# B_Arduino_MEGA2560_ref.net
KiCad netlist of a schematic drawn in EAGLE
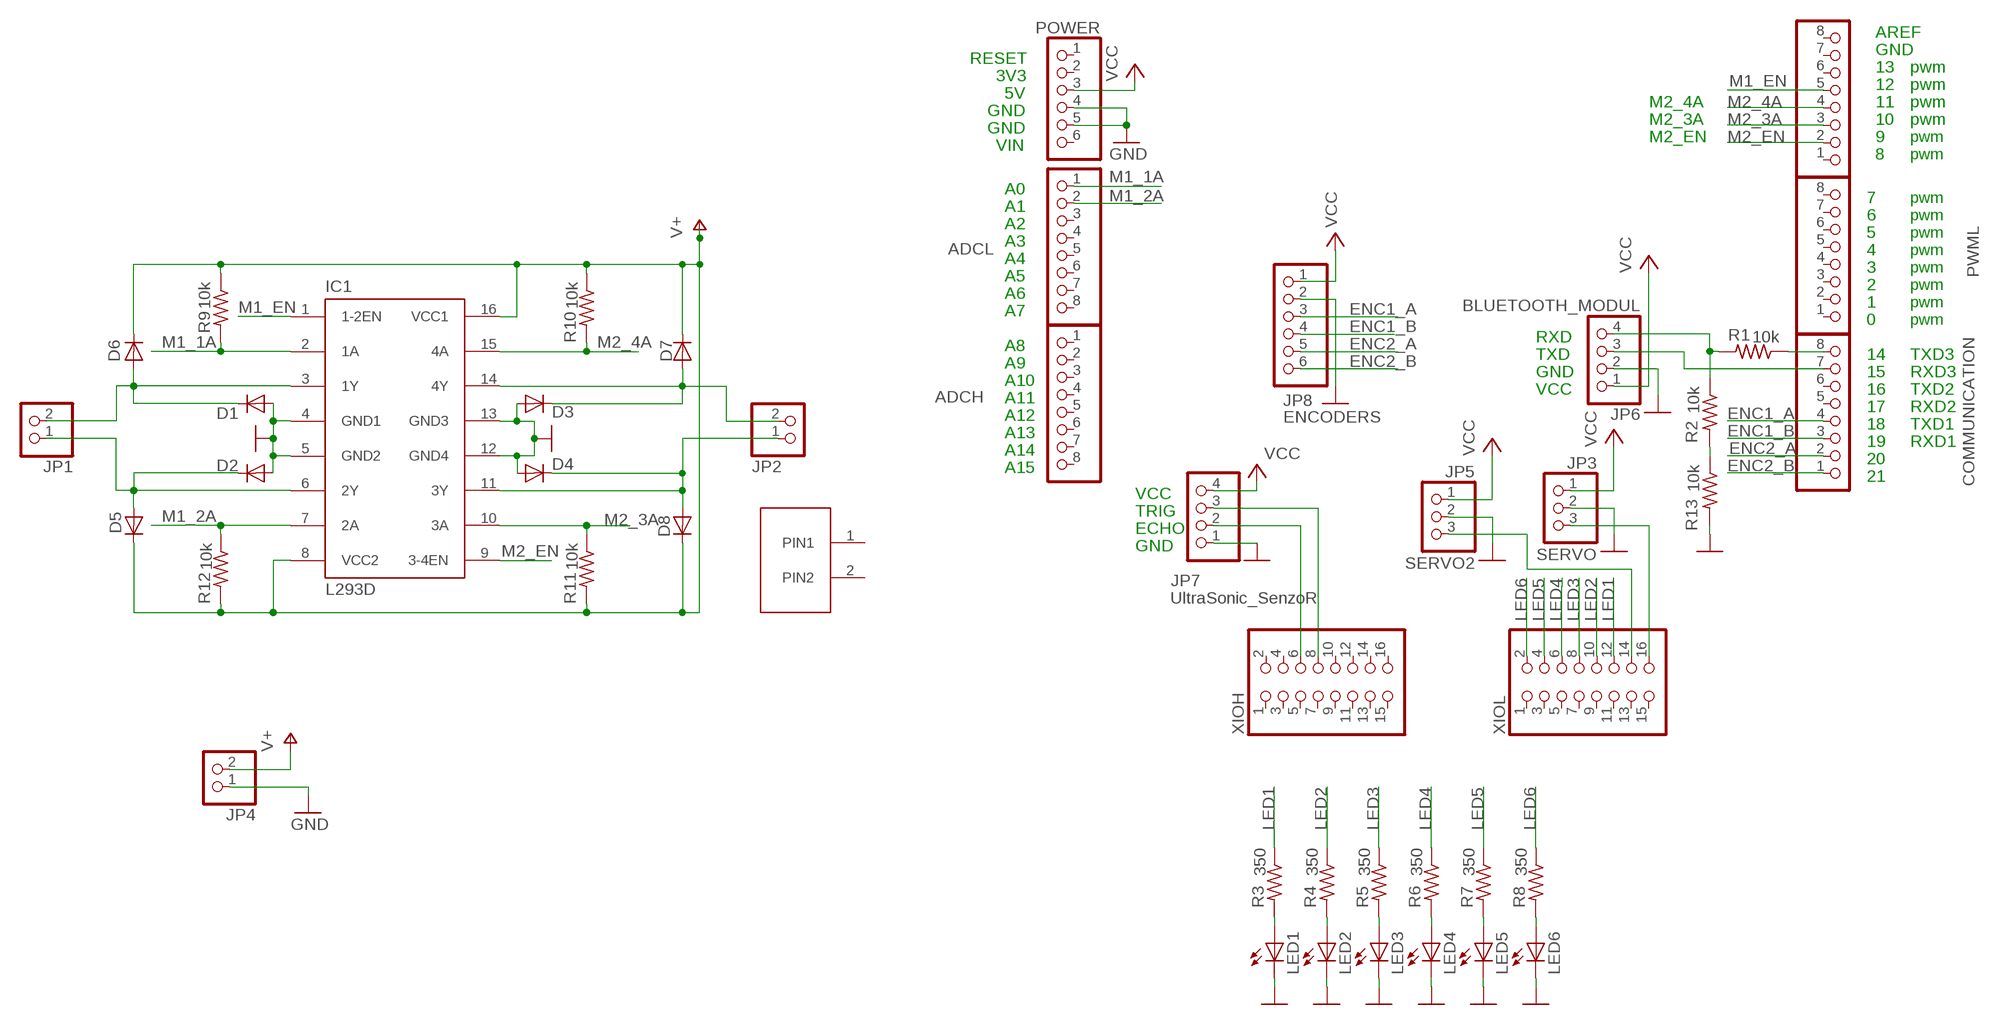
[diagram p0: schematic, sheet 1]

(export (version "E")
  (design (tool "Eeschema 10.0.6"))
  (components
    (comp (ref "ADCH")
      (value "PINHD-1X8")
      (footprint "eagle-import:1X08")
      (libsource (lib "eagle-import") (part "PINHD-1X8"))
    )
    (comp (ref "ADCL")
      (value "PINHD-1X8")
      (footprint "eagle-import:1X08")
      (libsource (lib "eagle-import") (part "PINHD-1X8"))
    )
    (comp (ref "COMMUNICATION")
      (value "PINHD-1X8")
      (footprint "eagle-import:1X08")
      (libsource (lib "eagle-import") (part "PINHD-1X8"))
    )
    (comp (ref "D1")
      (value "PMLL4150")
      (footprint "eagle-import:SOD80C")
      (libsource (lib "eagle-import") (part "PMLL4150"))
    )
    (comp (ref "D2")
      (value "PMLL4150")
      (footprint "eagle-import:SOD80C")
      (libsource (lib "eagle-import") (part "PMLL4150"))
    )
    (comp (ref "D3")
      (value "PMLL4150")
      (footprint "eagle-import:SOD80C")
      (libsource (lib "eagle-import") (part "PMLL4150"))
    )
    (comp (ref "D4")
      (value "PMLL4150")
      (footprint "eagle-import:SOD80C")
      (libsource (lib "eagle-import") (part "PMLL4150"))
    )
    (comp (ref "D5")
      (value "PMLL4150")
      (footprint "eagle-import:SOD80C")
      (libsource (lib "eagle-import") (part "PMLL4150"))
    )
    (comp (ref "D6")
      (value "PMLL4150")
      (footprint "eagle-import:SOD80C")
      (libsource (lib "eagle-import") (part "PMLL4150"))
    )
    (comp (ref "D7")
      (value "PMLL4150")
      (footprint "eagle-import:SOD80C")
      (libsource (lib "eagle-import") (part "PMLL4150"))
    )
    (comp (ref "D8")
      (value "PMLL4150")
      (footprint "eagle-import:SOD80C")
      (libsource (lib "eagle-import") (part "PMLL4150"))
    )
    (comp (ref "IC1")
      (value "L293D")
      (footprint "eagle-import:DIL16")
      (libsource (lib "eagle-import") (part "L293D"))
    )
    (comp (ref "JP1")
      (value "PINHD-1X2")
      (footprint "eagle-import:1X02")
      (libsource (lib "eagle-import") (part "PINHD-1X2"))
    )
    (comp (ref "JP2")
      (value "PINHD-1X2")
      (footprint "eagle-import:1X02")
      (libsource (lib "eagle-import") (part "PINHD-1X2"))
    )
    (comp (ref "JP3")
      (value "SERVO")
      (footprint "eagle-import:1X03")
      (libsource (lib "eagle-import") (part "PINHD-1X3"))
    )
    (comp (ref "JP4")
      (value "PINHD-1X2")
      (footprint "eagle-import:1X02")
      (libsource (lib "eagle-import") (part "PINHD-1X2"))
    )
    (comp (ref "JP5")
      (value "SERVO2")
      (footprint "eagle-import:1X03")
      (libsource (lib "eagle-import") (part "PINHD-1X3"))
    )
    (comp (ref "JP6")
      (value "BLUETOOTH_MODUL")
      (footprint "eagle-import:1X04")
      (libsource (lib "eagle-import") (part "PINHD-1X4"))
    )
    (comp (ref "JP7")
      (value "UltraSonic_SenzoR")
      (footprint "eagle-import:1X04")
      (libsource (lib "eagle-import") (part "PINHD-1X4"))
    )
    (comp (ref "JP8")
      (value "ENCODERS")
      (footprint "eagle-import:1X06")
      (libsource (lib "eagle-import") (part "PINHD-1X6"))
    )
    (comp (ref "LED1")
      (value "LED")
      (footprint "eagle-import:SMARTLED-TTW")
      (libsource (lib "eagle-import") (part "LED"))
    )
    (comp (ref "LED2")
      (value "LED")
      (footprint "eagle-import:SMARTLED-TTW")
      (libsource (lib "eagle-import") (part "LED"))
    )
    (comp (ref "LED3")
      (value "LED")
      (footprint "eagle-import:SMARTLED-TTW")
      (libsource (lib "eagle-import") (part "LED"))
    )
    (comp (ref "LED4")
      (value "LED")
      (footprint "eagle-import:SMARTLED-TTW")
      (libsource (lib "eagle-import") (part "LED"))
    )
    (comp (ref "LED5")
      (value "LED")
      (footprint "eagle-import:SMARTLED-TTW")
      (libsource (lib "eagle-import") (part "LED"))
    )
    (comp (ref "LED6")
      (value "LED")
      (footprint "eagle-import:SMARTLED-TTW")
      (libsource (lib "eagle-import") (part "LED"))
    )
    (comp (ref "POWER")
      (value "PINHD-1X6")
      (footprint "eagle-import:1X06")
      (libsource (lib "eagle-import") (part "PINHD-1X6"))
    )
    (comp (ref "PWMH")
      (value "PINHD-1X8")
      (footprint "eagle-import:1X08")
      (libsource (lib "eagle-import") (part "PINHD-1X8"))
    )
    (comp (ref "PWML")
      (value "PINHD-1X8")
      (footprint "eagle-import:1X08")
      (libsource (lib "eagle-import") (part "PINHD-1X8"))
    )
    (comp (ref "R1")
      (value "10k")
      (footprint "eagle-import:R0805")
      (libsource (lib "eagle-import") (part "R-US_R0805"))
    )
    (comp (ref "R2")
      (value "10k")
      (footprint "eagle-import:R0805")
      (libsource (lib "eagle-import") (part "R-US_R0805"))
    )
    (comp (ref "R3")
      (value "350")
      (footprint "eagle-import:R0805")
      (libsource (lib "eagle-import") (part "R-US_R0805"))
    )
    (comp (ref "R4")
      (value "350")
      (footprint "eagle-import:R0805")
      (libsource (lib "eagle-import") (part "R-US_R0805"))
    )
    (comp (ref "R5")
      (value "350")
      (footprint "eagle-import:R0805")
      (libsource (lib "eagle-import") (part "R-US_R0805"))
    )
    (comp (ref "R6")
      (value "350")
      (footprint "eagle-import:R0805")
      (libsource (lib "eagle-import") (part "R-US_R0805"))
    )
    (comp (ref "R7")
      (value "350")
      (footprint "eagle-import:R0805")
      (libsource (lib "eagle-import") (part "R-US_R0805"))
    )
    (comp (ref "R8")
      (value "350")
      (footprint "eagle-import:R0805")
      (libsource (lib "eagle-import") (part "R-US_R0805"))
    )
    (comp (ref "R9")
      (value "10k")
      (footprint "eagle-import:R0805")
      (libsource (lib "eagle-import") (part "R-US_R0805"))
    )
    (comp (ref "R10")
      (value "10k")
      (footprint "eagle-import:R0805")
      (libsource (lib "eagle-import") (part "R-US_R0805"))
    )
    (comp (ref "R11")
      (value "10k")
      (footprint "eagle-import:R0805")
      (libsource (lib "eagle-import") (part "R-US_R0805"))
    )
    (comp (ref "R12")
      (value "10k")
      (footprint "eagle-import:R0805")
      (libsource (lib "eagle-import") (part "R-US_R0805"))
    )
    (comp (ref "R13")
      (value "10k")
      (footprint "eagle-import:R0805")
      (libsource (lib "eagle-import") (part "R-US_R0805"))
    )
    (comp (ref "U$1")
      (value "FR_L_PNHD_2")
      (footprint "eagle-import:FR_L_PN_HD-2")
      (libsource (lib "eagle-import") (part "FR_L_PNHD_2"))
    )
    (comp (ref "XIOH")
      (value "PINHD-2X8")
      (footprint "eagle-import:2X08")
      (libsource (lib "eagle-import") (part "PINHD-2X8"))
    )
    (comp (ref "XIOL")
      (value "PINHD-2X8")
      (footprint "eagle-import:2X08")
      (libsource (lib "eagle-import") (part "PINHD-2X8"))
    )
  )
  (nets
    (net (code "1") (name "/ENC1_A") (class "Default")
      (node (ref "COMMUNICATION") (pin "4") (pinfunction "4_4") (pintype "passive"))
      (node (ref "JP8") (pin "3") (pinfunction "3_3") (pintype "passive"))
    )
    (net (code "2") (name "/ENC1_B") (class "Default")
      (node (ref "COMMUNICATION") (pin "3") (pinfunction "3_3") (pintype "passive"))
      (node (ref "JP8") (pin "4") (pinfunction "4_4") (pintype "passive"))
    )
    (net (code "3") (name "/ENC2_A") (class "Default")
      (node (ref "COMMUNICATION") (pin "2") (pinfunction "2_2") (pintype "passive"))
      (node (ref "JP8") (pin "5") (pinfunction "5_5") (pintype "passive"))
    )
    (net (code "4") (name "/ENC2_B") (class "Default")
      (node (ref "COMMUNICATION") (pin "1") (pinfunction "1_1") (pintype "passive"))
      (node (ref "JP8") (pin "6") (pinfunction "6_6") (pintype "passive"))
    )
    (net (code "5") (name "/LED1") (class "Default")
      (node (ref "R3") (pin "1") (pinfunction "1_1") (pintype "passive"))
      (node (ref "XIOL") (pin "12") (pinfunction "12_12") (pintype "passive"))
    )
    (net (code "6") (name "/LED2") (class "Default")
      (node (ref "R4") (pin "1") (pinfunction "1_1") (pintype "passive"))
      (node (ref "XIOL") (pin "10") (pinfunction "10_10") (pintype "passive"))
    )
    (net (code "7") (name "/LED3") (class "Default")
      (node (ref "R5") (pin "1") (pinfunction "1_1") (pintype "passive"))
      (node (ref "XIOL") (pin "8") (pinfunction "8_8") (pintype "passive"))
    )
    (net (code "8") (name "/LED4") (class "Default")
      (node (ref "R6") (pin "1") (pinfunction "1_1") (pintype "passive"))
      (node (ref "XIOL") (pin "6") (pinfunction "6_6") (pintype "passive"))
    )
    (net (code "9") (name "/LED5") (class "Default")
      (node (ref "R7") (pin "1") (pinfunction "1_1") (pintype "passive"))
      (node (ref "XIOL") (pin "4") (pinfunction "4_4") (pintype "passive"))
    )
    (net (code "10") (name "/LED6") (class "Default")
      (node (ref "R8") (pin "1") (pinfunction "1_1") (pintype "passive"))
      (node (ref "XIOL") (pin "2") (pinfunction "2_2") (pintype "passive"))
    )
    (net (code "11") (name "/M1_1A") (class "Default")
      (node (ref "ADCL") (pin "1") (pinfunction "1_1") (pintype "passive"))
      (node (ref "IC1") (pin "2") (pinfunction "1A_2") (pintype "input"))
      (node (ref "R9") (pin "2") (pinfunction "2_2") (pintype "passive"))
    )
    (net (code "12") (name "/M1_2A") (class "Default")
      (node (ref "ADCL") (pin "2") (pinfunction "2_2") (pintype "passive"))
      (node (ref "IC1") (pin "7") (pinfunction "2A_7") (pintype "input"))
      (node (ref "R12") (pin "1") (pinfunction "1_1") (pintype "passive"))
    )
    (net (code "13") (name "/M1_EN") (class "Default")
      (node (ref "IC1") (pin "1") (pinfunction "1-2EN_1") (pintype "input"))
      (node (ref "PWMH") (pin "5") (pinfunction "5_5") (pintype "passive"))
    )
    (net (code "14") (name "/M2_3A") (class "Default")
      (node (ref "IC1") (pin "10") (pinfunction "3A_10") (pintype "input"))
      (node (ref "PWMH") (pin "3") (pinfunction "3_3") (pintype "passive"))
      (node (ref "R11") (pin "1") (pinfunction "1_1") (pintype "passive"))
    )
    (net (code "15") (name "/M2_4A") (class "Default")
      (node (ref "IC1") (pin "15") (pinfunction "4A_15") (pintype "input"))
      (node (ref "PWMH") (pin "4") (pinfunction "4_4") (pintype "passive"))
      (node (ref "R10") (pin "2") (pinfunction "2_2") (pintype "passive"))
    )
    (net (code "16") (name "/M2_EN") (class "Default")
      (node (ref "IC1") (pin "9") (pinfunction "3-4EN_9") (pintype "input"))
      (node (ref "PWMH") (pin "2") (pinfunction "2_2") (pintype "passive"))
    )
    (net (code "17") (name "GND") (class "Default")
      (node (ref "D1") (pin "A") (pinfunction "A_A") (pintype "passive"))
      (node (ref "D2") (pin "A") (pinfunction "A_A") (pintype "passive"))
      (node (ref "D3") (pin "A") (pinfunction "A_A") (pintype "passive"))
      (node (ref "D4") (pin "A") (pinfunction "A_A") (pintype "passive"))
      (node (ref "IC1") (pin "12") (pinfunction "GND4_12") (pintype "power_in"))
      (node (ref "IC1") (pin "13") (pinfunction "GND3_13") (pintype "power_in"))
      (node (ref "IC1") (pin "4") (pinfunction "GND1_4") (pintype "power_in"))
      (node (ref "IC1") (pin "5") (pinfunction "GND2_5") (pintype "power_in"))
      (node (ref "JP3") (pin "2") (pinfunction "2_2") (pintype "passive"))
      (node (ref "JP4") (pin "1") (pinfunction "1_1") (pintype "passive"))
      (node (ref "JP5") (pin "2") (pinfunction "2_2") (pintype "passive"))
      (node (ref "JP6") (pin "2") (pinfunction "2_2") (pintype "passive"))
      (node (ref "JP7") (pin "1") (pinfunction "1_1") (pintype "passive"))
      (node (ref "JP8") (pin "2") (pinfunction "2_2") (pintype "passive"))
      (node (ref "LED1") (pin "C@1") (pinfunction "C_C@1") (pintype "passive"))
      (node (ref "LED2") (pin "C@1") (pinfunction "C_C@1") (pintype "passive"))
      (node (ref "LED3") (pin "C@1") (pinfunction "C_C@1") (pintype "passive"))
      (node (ref "LED4") (pin "C@1") (pinfunction "C_C@1") (pintype "passive"))
      (node (ref "LED5") (pin "C@1") (pinfunction "C_C@1") (pintype "passive"))
      (node (ref "LED6") (pin "C@1") (pinfunction "C_C@1") (pintype "passive"))
      (node (ref "POWER") (pin "4") (pinfunction "4_4") (pintype "passive"))
      (node (ref "POWER") (pin "5") (pinfunction "5_5") (pintype "passive"))
      (node (ref "R13") (pin "2") (pinfunction "2_2") (pintype "passive"))
    )
    (net (code "18") (name "Net-(COMMUNICATION-Pad7)") (class "Default")
      (node (ref "COMMUNICATION") (pin "7") (pinfunction "7_7") (pintype "passive"))
      (node (ref "JP6") (pin "3") (pinfunction "3_3") (pintype "passive"))
    )
    (net (code "19") (name "Net-(COMMUNICATION-Pad8)") (class "Default")
      (node (ref "COMMUNICATION") (pin "8") (pinfunction "8_8") (pintype "passive"))
      (node (ref "R1") (pin "1") (pinfunction "1_1") (pintype "passive"))
    )
    (net (code "20") (name "Net-(IC1-1Y)") (class "Default")
      (node (ref "D1") (pin "C") (pinfunction "C_C") (pintype "passive"))
      (node (ref "D6") (pin "A") (pinfunction "A_A") (pintype "passive"))
      (node (ref "IC1") (pin "3") (pinfunction "1Y_3") (pintype "output"))
      (node (ref "JP1") (pin "2") (pinfunction "2_2") (pintype "passive"))
    )
    (net (code "21") (name "Net-(IC1-2Y)") (class "Default")
      (node (ref "D2") (pin "C") (pinfunction "C_C") (pintype "passive"))
      (node (ref "D5") (pin "A") (pinfunction "A_A") (pintype "passive"))
      (node (ref "IC1") (pin "6") (pinfunction "2Y_6") (pintype "output"))
      (node (ref "JP1") (pin "1") (pinfunction "1_1") (pintype "passive"))
    )
    (net (code "22") (name "Net-(IC1-3Y)") (class "Default")
      (node (ref "D4") (pin "C") (pinfunction "C_C") (pintype "passive"))
      (node (ref "D8") (pin "A") (pinfunction "A_A") (pintype "passive"))
      (node (ref "IC1") (pin "11") (pinfunction "3Y_11") (pintype "output"))
      (node (ref "JP2") (pin "1") (pinfunction "1_1") (pintype "passive"))
    )
    (net (code "23") (name "Net-(IC1-4Y)") (class "Default")
      (node (ref "D3") (pin "C") (pinfunction "C_C") (pintype "passive"))
      (node (ref "D7") (pin "A") (pinfunction "A_A") (pintype "passive"))
      (node (ref "IC1") (pin "14") (pinfunction "4Y_14") (pintype "output"))
      (node (ref "JP2") (pin "2") (pinfunction "2_2") (pintype "passive"))
    )
    (net (code "24") (name "Net-(JP3-Pad3)") (class "Default")
      (node (ref "JP3") (pin "3") (pinfunction "3_3") (pintype "passive"))
      (node (ref "XIOL") (pin "16") (pinfunction "16_16") (pintype "passive"))
    )
    (net (code "25") (name "Net-(JP5-Pad3)") (class "Default")
      (node (ref "JP5") (pin "3") (pinfunction "3_3") (pintype "passive"))
      (node (ref "XIOL") (pin "14") (pinfunction "14_14") (pintype "passive"))
    )
    (net (code "26") (name "Net-(JP6-Pad4)") (class "Default")
      (node (ref "JP6") (pin "4") (pinfunction "4_4") (pintype "passive"))
      (node (ref "R1") (pin "2") (pinfunction "2_2") (pintype "passive"))
      (node (ref "R2") (pin "1") (pinfunction "1_1") (pintype "passive"))
    )
    (net (code "27") (name "Net-(JP7-Pad2)") (class "Default")
      (node (ref "JP7") (pin "2") (pinfunction "2_2") (pintype "passive"))
      (node (ref "XIOH") (pin "6") (pinfunction "6_6") (pintype "passive"))
    )
    (net (code "28") (name "Net-(JP7-Pad3)") (class "Default")
      (node (ref "JP7") (pin "3") (pinfunction "3_3") (pintype "passive"))
      (node (ref "XIOH") (pin "8") (pinfunction "8_8") (pintype "passive"))
    )
    (net (code "29") (name "Net-(LED1-A)") (class "Default")
      (node (ref "LED1") (pin "A@1") (pinfunction "A_A@1") (pintype "passive"))
      (node (ref "R3") (pin "2") (pinfunction "2_2") (pintype "passive"))
    )
    (net (code "30") (name "Net-(LED2-A)") (class "Default")
      (node (ref "LED2") (pin "A@1") (pinfunction "A_A@1") (pintype "passive"))
      (node (ref "R4") (pin "2") (pinfunction "2_2") (pintype "passive"))
    )
    (net (code "31") (name "Net-(LED3-A)") (class "Default")
      (node (ref "LED3") (pin "A@1") (pinfunction "A_A@1") (pintype "passive"))
      (node (ref "R5") (pin "2") (pinfunction "2_2") (pintype "passive"))
    )
    (net (code "32") (name "Net-(LED4-A)") (class "Default")
      (node (ref "LED4") (pin "A@1") (pinfunction "A_A@1") (pintype "passive"))
      (node (ref "R6") (pin "2") (pinfunction "2_2") (pintype "passive"))
    )
    (net (code "33") (name "Net-(LED5-A)") (class "Default")
      (node (ref "LED5") (pin "A@1") (pinfunction "A_A@1") (pintype "passive"))
      (node (ref "R7") (pin "2") (pinfunction "2_2") (pintype "passive"))
    )
    (net (code "34") (name "Net-(LED6-A)") (class "Default")
      (node (ref "LED6") (pin "A@1") (pinfunction "A_A@1") (pintype "passive"))
      (node (ref "R8") (pin "2") (pinfunction "2_2") (pintype "passive"))
    )
    (net (code "35") (name "Net-(R13-Pad1)") (class "Default")
      (node (ref "R13") (pin "1") (pinfunction "1_1") (pintype "passive"))
      (node (ref "R2") (pin "2") (pinfunction "2_2") (pintype "passive"))
    )
    (net (code "36") (name "V+") (class "Default")
      (node (ref "D5") (pin "C") (pinfunction "C_C") (pintype "passive"))
      (node (ref "D6") (pin "C") (pinfunction "C_C") (pintype "passive"))
      (node (ref "D7") (pin "C") (pinfunction "C_C") (pintype "passive"))
      (node (ref "D8") (pin "C") (pinfunction "C_C") (pintype "passive"))
      (node (ref "IC1") (pin "16") (pinfunction "VCC1_16") (pintype "power_in"))
      (node (ref "IC1") (pin "8") (pinfunction "VCC2_8") (pintype "power_in"))
      (node (ref "JP4") (pin "2") (pinfunction "2_2") (pintype "passive"))
      (node (ref "R10") (pin "1") (pinfunction "1_1") (pintype "passive"))
      (node (ref "R11") (pin "2") (pinfunction "2_2") (pintype "passive"))
      (node (ref "R12") (pin "2") (pinfunction "2_2") (pintype "passive"))
      (node (ref "R9") (pin "1") (pinfunction "1_1") (pintype "passive"))
    )
    (net (code "37") (name "VCC") (class "Default")
      (node (ref "JP3") (pin "1") (pinfunction "1_1") (pintype "passive"))
      (node (ref "JP5") (pin "1") (pinfunction "1_1") (pintype "passive"))
      (node (ref "JP6") (pin "1") (pinfunction "1_1") (pintype "passive"))
      (node (ref "JP7") (pin "4") (pinfunction "4_4") (pintype "passive"))
      (node (ref "JP8") (pin "1") (pinfunction "1_1") (pintype "passive"))
      (node (ref "POWER") (pin "3") (pinfunction "3_3") (pintype "passive"))
    )
    (net (code "38") (name "unconnected-(ADCH-Pad1)") (class "Default")
      (node (ref "ADCH") (pin "1") (pinfunction "1_1") (pintype "passive"))
    )
    (net (code "39") (name "unconnected-(ADCH-Pad2)") (class "Default")
      (node (ref "ADCH") (pin "2") (pinfunction "2_2") (pintype "passive"))
    )
    (net (code "40") (name "unconnected-(ADCH-Pad3)") (class "Default")
      (node (ref "ADCH") (pin "3") (pinfunction "3_3") (pintype "passive"))
    )
    (net (code "41") (name "unconnected-(ADCH-Pad4)") (class "Default")
      (node (ref "ADCH") (pin "4") (pinfunction "4_4") (pintype "passive"))
    )
    (net (code "42") (name "unconnected-(ADCH-Pad5)") (class "Default")
      (node (ref "ADCH") (pin "5") (pinfunction "5_5") (pintype "passive"))
    )
    (net (code "43") (name "unconnected-(ADCH-Pad6)") (class "Default")
      (node (ref "ADCH") (pin "6") (pinfunction "6_6") (pintype "passive"))
    )
    (net (code "44") (name "unconnected-(ADCH-Pad7)") (class "Default")
      (node (ref "ADCH") (pin "7") (pinfunction "7_7") (pintype "passive"))
    )
    (net (code "45") (name "unconnected-(ADCH-Pad8)") (class "Default")
      (node (ref "ADCH") (pin "8") (pinfunction "8_8") (pintype "passive"))
    )
    (net (code "46") (name "unconnected-(ADCL-Pad3)") (class "Default")
      (node (ref "ADCL") (pin "3") (pinfunction "3_3") (pintype "passive"))
    )
    (net (code "47") (name "unconnected-(ADCL-Pad4)") (class "Default")
      (node (ref "ADCL") (pin "4") (pinfunction "4_4") (pintype "passive"))
    )
    (net (code "48") (name "unconnected-(ADCL-Pad5)") (class "Default")
      (node (ref "ADCL") (pin "5") (pinfunction "5_5") (pintype "passive"))
    )
    (net (code "49") (name "unconnected-(ADCL-Pad6)") (class "Default")
      (node (ref "ADCL") (pin "6") (pinfunction "6_6") (pintype "passive"))
    )
    (net (code "50") (name "unconnected-(ADCL-Pad7)") (class "Default")
      (node (ref "ADCL") (pin "7") (pinfunction "7_7") (pintype "passive"))
    )
    (net (code "51") (name "unconnected-(ADCL-Pad8)") (class "Default")
      (node (ref "ADCL") (pin "8") (pinfunction "8_8") (pintype "passive"))
    )
    (net (code "52") (name "unconnected-(COMMUNICATION-Pad5)") (class "Default")
      (node (ref "COMMUNICATION") (pin "5") (pinfunction "5_5") (pintype "passive"))
    )
    (net (code "53") (name "unconnected-(COMMUNICATION-Pad6)") (class "Default")
      (node (ref "COMMUNICATION") (pin "6") (pinfunction "6_6") (pintype "passive"))
    )
    (net (code "54") (name "unconnected-(POWER-Pad1)") (class "Default")
      (node (ref "POWER") (pin "1") (pinfunction "1_1") (pintype "passive"))
    )
    (net (code "55") (name "unconnected-(POWER-Pad2)") (class "Default")
      (node (ref "POWER") (pin "2") (pinfunction "2_2") (pintype "passive"))
    )
    (net (code "56") (name "unconnected-(POWER-Pad6)") (class "Default")
      (node (ref "POWER") (pin "6") (pinfunction "6_6") (pintype "passive"))
    )
    (net (code "57") (name "unconnected-(PWMH-Pad1)") (class "Default")
      (node (ref "PWMH") (pin "1") (pinfunction "1_1") (pintype "passive"))
    )
    (net (code "58") (name "unconnected-(PWMH-Pad6)") (class "Default")
      (node (ref "PWMH") (pin "6") (pinfunction "6_6") (pintype "passive"))
    )
    (net (code "59") (name "unconnected-(PWMH-Pad7)") (class "Default")
      (node (ref "PWMH") (pin "7") (pinfunction "7_7") (pintype "passive"))
    )
    (net (code "60") (name "unconnected-(PWMH-Pad8)") (class "Default")
      (node (ref "PWMH") (pin "8") (pinfunction "8_8") (pintype "passive"))
    )
    (net (code "61") (name "unconnected-(PWML-Pad1)") (class "Default")
      (node (ref "PWML") (pin "1") (pinfunction "1_1") (pintype "passive"))
    )
    (net (code "62") (name "unconnected-(PWML-Pad2)") (class "Default")
      (node (ref "PWML") (pin "2") (pinfunction "2_2") (pintype "passive"))
    )
    (net (code "63") (name "unconnected-(PWML-Pad3)") (class "Default")
      (node (ref "PWML") (pin "3") (pinfunction "3_3") (pintype "passive"))
    )
    (net (code "64") (name "unconnected-(PWML-Pad4)") (class "Default")
      (node (ref "PWML") (pin "4") (pinfunction "4_4") (pintype "passive"))
    )
    (net (code "65") (name "unconnected-(PWML-Pad5)") (class "Default")
      (node (ref "PWML") (pin "5") (pinfunction "5_5") (pintype "passive"))
    )
    (net (code "66") (name "unconnected-(PWML-Pad6)") (class "Default")
      (node (ref "PWML") (pin "6") (pinfunction "6_6") (pintype "passive"))
    )
    (net (code "67") (name "unconnected-(PWML-Pad7)") (class "Default")
      (node (ref "PWML") (pin "7") (pinfunction "7_7") (pintype "passive"))
    )
    (net (code "68") (name "unconnected-(PWML-Pad8)") (class "Default")
      (node (ref "PWML") (pin "8") (pinfunction "8_8") (pintype "passive"))
    )
    (net (code "69") (name "unconnected-(U$1-PIN1-Pad1)") (class "Default")
      (node (ref "U$1") (pin "1") (pinfunction "PIN1_1") (pintype "bidirectional"))
    )
    (net (code "70") (name "unconnected-(U$1-PIN2-Pad2)") (class "Default")
      (node (ref "U$1") (pin "2") (pinfunction "PIN2_2") (pintype "bidirectional"))
    )
    (net (code "71") (name "unconnected-(XIOH-Pad1)") (class "Default")
      (node (ref "XIOH") (pin "1") (pinfunction "1_1") (pintype "passive"))
    )
    (net (code "72") (name "unconnected-(XIOH-Pad2)") (class "Default")
      (node (ref "XIOH") (pin "2") (pinfunction "2_2") (pintype "passive"))
    )
    (net (code "73") (name "unconnected-(XIOH-Pad3)") (class "Default")
      (node (ref "XIOH") (pin "3") (pinfunction "3_3") (pintype "passive"))
    )
    (net (code "74") (name "unconnected-(XIOH-Pad4)") (class "Default")
      (node (ref "XIOH") (pin "4") (pinfunction "4_4") (pintype "passive"))
    )
    (net (code "75") (name "unconnected-(XIOH-Pad5)") (class "Default")
      (node (ref "XIOH") (pin "5") (pinfunction "5_5") (pintype "passive"))
    )
    (net (code "76") (name "unconnected-(XIOH-Pad7)") (class "Default")
      (node (ref "XIOH") (pin "7") (pinfunction "7_7") (pintype "passive"))
    )
    (net (code "77") (name "unconnected-(XIOH-Pad9)") (class "Default")
      (node (ref "XIOH") (pin "9") (pinfunction "9_9") (pintype "passive"))
    )
    (net (code "78") (name "unconnected-(XIOH-Pad10)") (class "Default")
      (node (ref "XIOH") (pin "10") (pinfunction "10_10") (pintype "passive"))
    )
    (net (code "79") (name "unconnected-(XIOH-Pad11)") (class "Default")
      (node (ref "XIOH") (pin "11") (pinfunction "11_11") (pintype "passive"))
    )
    (net (code "80") (name "unconnected-(XIOH-Pad12)") (class "Default")
      (node (ref "XIOH") (pin "12") (pinfunction "12_12") (pintype "passive"))
    )
    (net (code "81") (name "unconnected-(XIOH-Pad13)") (class "Default")
      (node (ref "XIOH") (pin "13") (pinfunction "13_13") (pintype "passive"))
    )
    (net (code "82") (name "unconnected-(XIOH-Pad14)") (class "Default")
      (node (ref "XIOH") (pin "14") (pinfunction "14_14") (pintype "passive"))
    )
    (net (code "83") (name "unconnected-(XIOH-Pad15)") (class "Default")
      (node (ref "XIOH") (pin "15") (pinfunction "15_15") (pintype "passive"))
    )
    (net (code "84") (name "unconnected-(XIOH-Pad16)") (class "Default")
      (node (ref "XIOH") (pin "16") (pinfunction "16_16") (pintype "passive"))
    )
    (net (code "85") (name "unconnected-(XIOL-Pad1)") (class "Default")
      (node (ref "XIOL") (pin "1") (pinfunction "1_1") (pintype "passive"))
    )
    (net (code "86") (name "unconnected-(XIOL-Pad3)") (class "Default")
      (node (ref "XIOL") (pin "3") (pinfunction "3_3") (pintype "passive"))
    )
    (net (code "87") (name "unconnected-(XIOL-Pad5)") (class "Default")
      (node (ref "XIOL") (pin "5") (pinfunction "5_5") (pintype "passive"))
    )
    (net (code "88") (name "unconnected-(XIOL-Pad7)") (class "Default")
      (node (ref "XIOL") (pin "7") (pinfunction "7_7") (pintype "passive"))
    )
    (net (code "89") (name "unconnected-(XIOL-Pad9)") (class "Default")
      (node (ref "XIOL") (pin "9") (pinfunction "9_9") (pintype "passive"))
    )
    (net (code "90") (name "unconnected-(XIOL-Pad11)") (class "Default")
      (node (ref "XIOL") (pin "11") (pinfunction "11_11") (pintype "passive"))
    )
    (net (code "91") (name "unconnected-(XIOL-Pad13)") (class "Default")
      (node (ref "XIOL") (pin "13") (pinfunction "13_13") (pintype "passive"))
    )
    (net (code "92") (name "unconnected-(XIOL-Pad15)") (class "Default")
      (node (ref "XIOL") (pin "15") (pinfunction "15_15") (pintype "passive"))
    )
  )
)
